# WS2801-Breakout-v10.net
KiCad netlist of a schematic drawn in EAGLE
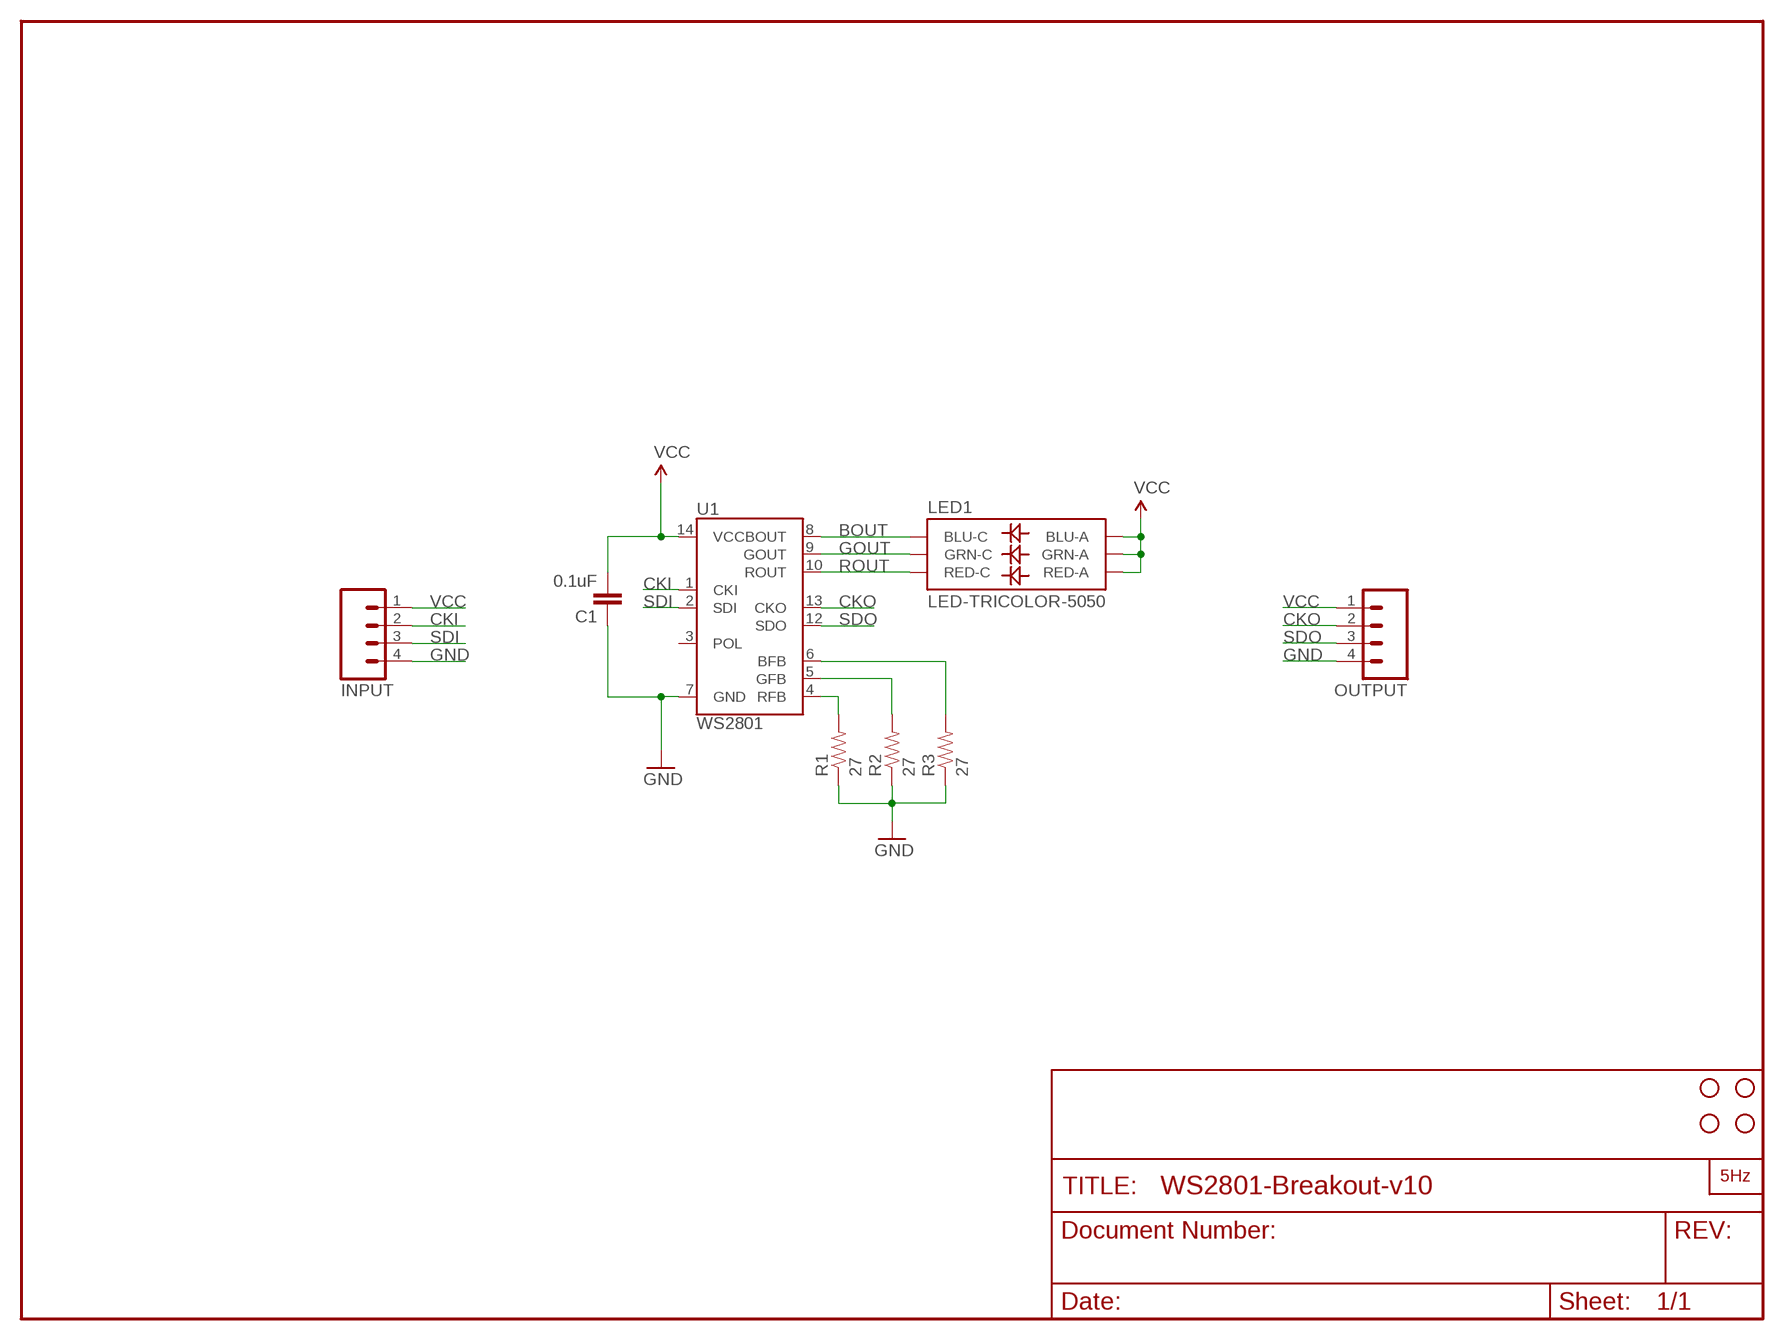
[diagram p0: schematic, sheet 1]

(export (version "E")
  (design (tool "Eeschema 10.0.6"))
  (components
    (comp (ref "C1")
      (value "0.1uF")
      (footprint "eagle-import:0402-CAP")
      (libsource (lib "eagle-import") (part "CAP0402-CAP"))
    )
    (comp (ref "INPUT")
      (value "M04PTH")
      (footprint "eagle-import:1X04")
      (libsource (lib "eagle-import") (part "M04PTH"))
    )
    (comp (ref "JP1")
      (value "STAND-OFF")
      (footprint "eagle-import:STAND-OFF")
      (libsource (lib "eagle-import") (part "STAND-OFF"))
    )
    (comp (ref "JP2")
      (value "STAND-OFF")
      (footprint "eagle-import:STAND-OFF")
      (libsource (lib "eagle-import") (part "STAND-OFF"))
    )
    (comp (ref "JP4")
      (value "STAND-OFF")
      (footprint "eagle-import:STAND-OFF")
      (libsource (lib "eagle-import") (part "STAND-OFF"))
    )
    (comp (ref "JP5")
      (value "STAND-OFF")
      (footprint "eagle-import:STAND-OFF")
      (libsource (lib "eagle-import") (part "STAND-OFF"))
    )
    (comp (ref "LED1")
      (value "LED-TRICOLOR-5050")
      (footprint "eagle-import:LED-TRICOLOR-5050")
      (libsource (lib "eagle-import") (part "LED-TRICOLOR-5050"))
    )
    (comp (ref "OUTPUT")
      (value "M04PTH")
      (footprint "eagle-import:1X04")
      (libsource (lib "eagle-import") (part "M04PTH"))
    )
    (comp (ref "R1")
      (value "27")
      (footprint "eagle-import:0402-RES")
      (libsource (lib "eagle-import") (part "RESISTOR0402-RES"))
    )
    (comp (ref "R2")
      (value "27")
      (footprint "eagle-import:0402-RES")
      (libsource (lib "eagle-import") (part "RESISTOR0402-RES"))
    )
    (comp (ref "R3")
      (value "27")
      (footprint "eagle-import:0402-RES")
      (libsource (lib "eagle-import") (part "RESISTOR0402-RES"))
    )
    (comp (ref "U$1")
      (value "LOGO2_SILKC5MM")
      (footprint "eagle-import:CIRCULO2_5MM")
      (libsource (lib "eagle-import") (part "LOGO2_SILKC5MM"))
    )
    (comp (ref "U1")
      (value "WS2801")
      (footprint "eagle-import:SOP-14")
      (libsource (lib "eagle-import") (part "WS2801"))
    )
  )
  (nets
    (net (code "1") (name "/BOUT") (class "Default")
      (node (ref "LED1") (pin "4") (pinfunction "BLU-C_4") (pintype "bidirectional"))
      (node (ref "U1") (pin "8") (pinfunction "BOUT_8") (pintype "bidirectional"))
    )
    (net (code "2") (name "/CKI") (class "Default")
      (node (ref "INPUT") (pin "2") (pinfunction "2_2") (pintype "passive"))
      (node (ref "U1") (pin "1") (pinfunction "CKI_1") (pintype "bidirectional"))
    )
    (net (code "3") (name "/CKO") (class "Default")
      (node (ref "OUTPUT") (pin "2") (pinfunction "2_2") (pintype "passive"))
      (node (ref "U1") (pin "13") (pinfunction "CKO_13") (pintype "bidirectional"))
    )
    (net (code "4") (name "/GOUT") (class "Default")
      (node (ref "LED1") (pin "6") (pinfunction "GRN-C_6") (pintype "bidirectional"))
      (node (ref "U1") (pin "9") (pinfunction "GOUT_9") (pintype "bidirectional"))
    )
    (net (code "5") (name "/ROUT") (class "Default")
      (node (ref "LED1") (pin "5") (pinfunction "RED-C_5") (pintype "bidirectional"))
      (node (ref "U1") (pin "10") (pinfunction "ROUT_10") (pintype "bidirectional"))
    )
    (net (code "6") (name "/SDI") (class "Default")
      (node (ref "INPUT") (pin "3") (pinfunction "3_3") (pintype "passive"))
      (node (ref "U1") (pin "2") (pinfunction "SDI_2") (pintype "bidirectional"))
    )
    (net (code "7") (name "/SDO") (class "Default")
      (node (ref "OUTPUT") (pin "3") (pinfunction "3_3") (pintype "passive"))
      (node (ref "U1") (pin "12") (pinfunction "SDO_12") (pintype "bidirectional"))
    )
    (net (code "8") (name "GND") (class "Default")
      (node (ref "C1") (pin "1") (pinfunction "1_1") (pintype "passive"))
      (node (ref "INPUT") (pin "4") (pinfunction "4_4") (pintype "passive"))
      (node (ref "OUTPUT") (pin "4") (pinfunction "4_4") (pintype "passive"))
      (node (ref "R1") (pin "1") (pinfunction "1_1") (pintype "passive"))
      (node (ref "R2") (pin "1") (pinfunction "1_1") (pintype "passive"))
      (node (ref "R3") (pin "1") (pinfunction "1_1") (pintype "passive"))
      (node (ref "U1") (pin "7") (pinfunction "GND_7") (pintype "bidirectional"))
    )
    (net (code "9") (name "Net-(U1-BFB)") (class "Default")
      (node (ref "R3") (pin "2") (pinfunction "2_2") (pintype "passive"))
      (node (ref "U1") (pin "6") (pinfunction "BFB_6") (pintype "bidirectional"))
    )
    (net (code "10") (name "Net-(U1-GFB)") (class "Default")
      (node (ref "R2") (pin "2") (pinfunction "2_2") (pintype "passive"))
      (node (ref "U1") (pin "5") (pinfunction "GFB_5") (pintype "bidirectional"))
    )
    (net (code "11") (name "Net-(U1-RFB)") (class "Default")
      (node (ref "R1") (pin "2") (pinfunction "2_2") (pintype "passive"))
      (node (ref "U1") (pin "4") (pinfunction "RFB_4") (pintype "bidirectional"))
    )
    (net (code "12") (name "VCC") (class "Default")
      (node (ref "C1") (pin "2") (pinfunction "2_2") (pintype "passive"))
      (node (ref "INPUT") (pin "1") (pinfunction "1_1") (pintype "passive"))
      (node (ref "LED1") (pin "1") (pinfunction "GRN-A_1") (pintype "bidirectional"))
      (node (ref "LED1") (pin "2") (pinfunction "RED-A_2") (pintype "bidirectional"))
      (node (ref "LED1") (pin "3") (pinfunction "BLU-A_3") (pintype "bidirectional"))
      (node (ref "OUTPUT") (pin "1") (pinfunction "1_1") (pintype "passive"))
      (node (ref "U1") (pin "14") (pinfunction "VCC_14") (pintype "bidirectional"))
    )
    (net (code "13") (name "unconnected-(U1-POL-Pad3)") (class "Default")
      (node (ref "U1") (pin "3") (pinfunction "POL_3") (pintype "bidirectional"))
    )
  )
)
